# GenRF_R00.net
KiCad netlist of a schematic drawn in Altium Designer
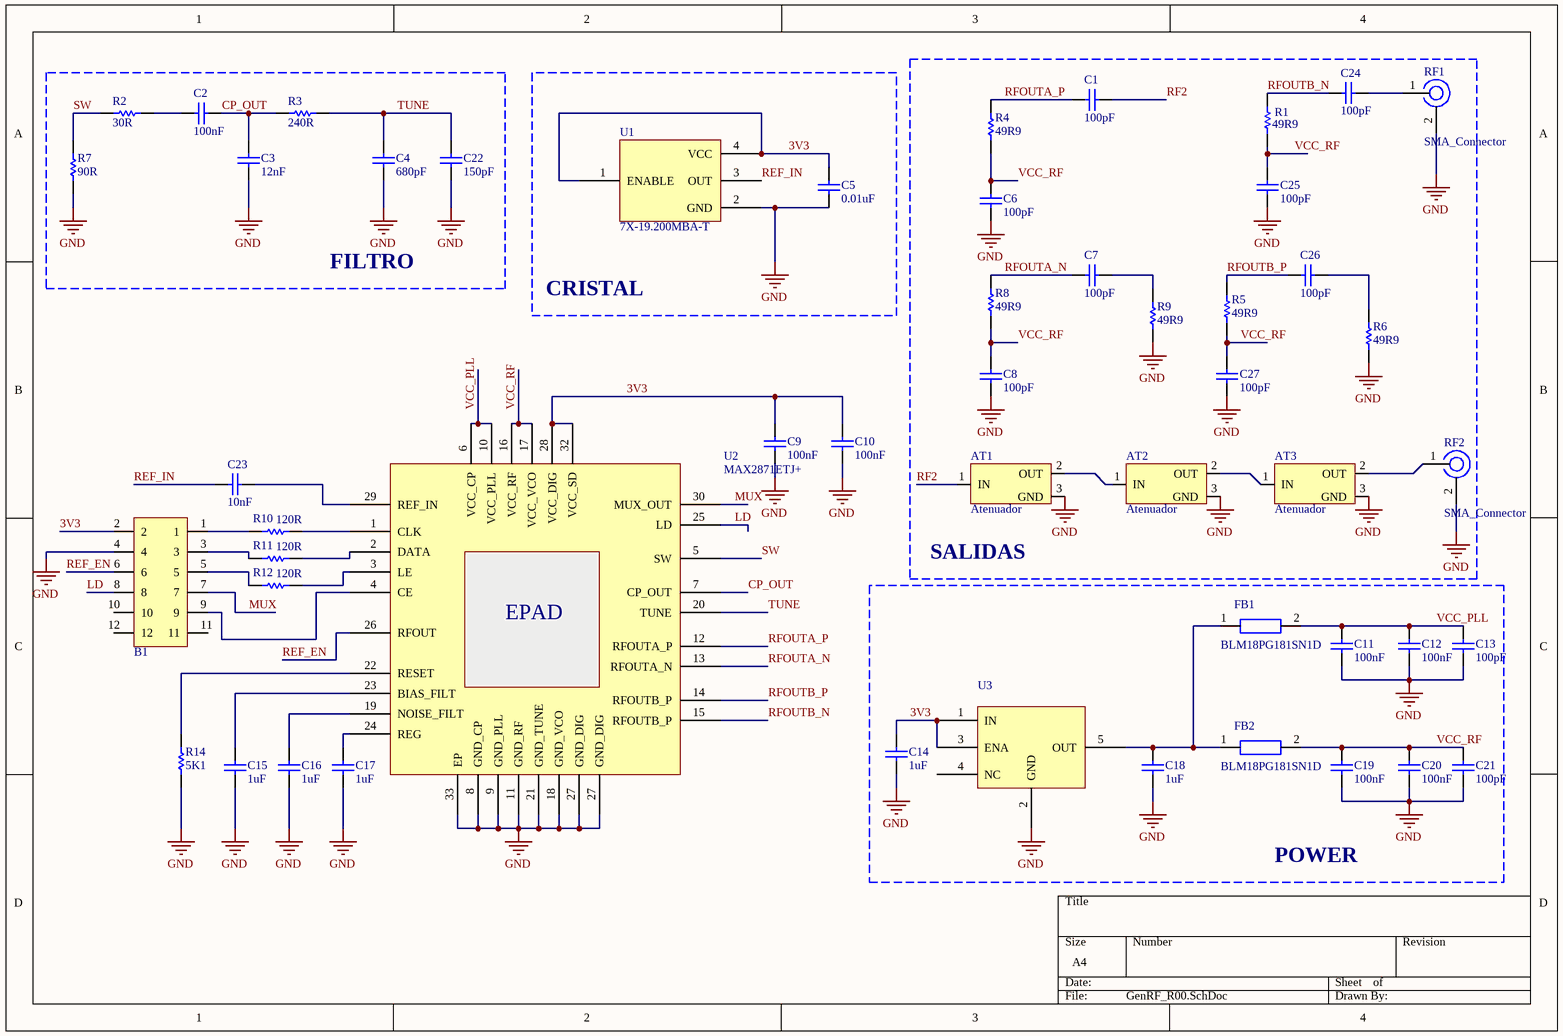
[diagram p0: GenRF_R00.SchDoc]

(export (version "E")
  (design (tool "Eeschema 10.0.6"))
  (components
    (comp (ref "AT1")
      (value "Atenuador")
      (footprint "Attenuator 0603")
      (libsource (lib "SchLib_PocketAnalyzer") (part "Atenuador"))
    )
    (comp (ref "AT2")
      (value "Atenuador")
      (footprint "Attenuator 0603")
      (libsource (lib "SchLib_PocketAnalyzer") (part "Atenuador"))
    )
    (comp (ref "AT3")
      (value "Atenuador")
      (footprint "Attenuator 0603")
      (libsource (lib "SchLib_PocketAnalyzer") (part "Atenuador"))
    )
    (comp (ref "B1")
      (value "Tira de pines de 12")
      (footprint "Header_M_2x6_0.1\"")
      (libsource (lib "GenRF_R00") (part "Headpin 10"))
    )
    (comp (ref "C1")
      (value "100pF")
      (footprint "C_0603")
      (description "Capacitor")
      (libsource (lib "Simulation Generic Components") (part "Capacitor"))
    )
    (comp (ref "C2")
      (value "100nF")
      (footprint "C_0805")
      (description "Capacitor")
      (libsource (lib "Simulation Generic Components") (part "Capacitor"))
    )
    (comp (ref "C3")
      (value "12nF")
      (footprint "C_0805")
      (description "Capacitor")
      (libsource (lib "Simulation Generic Components") (part "Capacitor"))
    )
    (comp (ref "C4")
      (value "680pF")
      (footprint "C_0805")
      (description "Capacitor")
      (libsource (lib "Simulation Generic Components") (part "Capacitor"))
    )
    (comp (ref "C5")
      (value "0.01uF")
      (footprint "C_0805")
      (description "Capacitor")
      (libsource (lib "Simulation Generic Components") (part "Capacitor"))
    )
    (comp (ref "C6")
      (value "100pF")
      (footprint "C_0805")
      (description "Capacitor")
      (libsource (lib "Simulation Generic Components") (part "Capacitor"))
    )
    (comp (ref "C7")
      (value "100pF")
      (footprint "C_0603")
      (description "Capacitor")
      (libsource (lib "Simulation Generic Components") (part "Capacitor"))
    )
    (comp (ref "C8")
      (value "100pF")
      (footprint "C_0805")
      (description "Capacitor")
      (libsource (lib "Simulation Generic Components") (part "Capacitor"))
    )
    (comp (ref "C9")
      (value "100nF")
      (footprint "C_0805")
      (description "Capacitor")
      (libsource (lib "Simulation Generic Components") (part "Capacitor"))
    )
    (comp (ref "C10")
      (value "100nF")
      (footprint "C_0805")
      (description "Capacitor")
      (libsource (lib "Simulation Generic Components") (part "Capacitor"))
    )
    (comp (ref "C11")
      (value "100nF")
      (footprint "C_0805")
      (description "Capacitor")
      (libsource (lib "Simulation Generic Components") (part "Capacitor"))
    )
    (comp (ref "C12")
      (value "100nF")
      (footprint "C_0805")
      (description "Capacitor")
      (libsource (lib "Simulation Generic Components") (part "Capacitor"))
    )
    (comp (ref "C13")
      (value "100pF")
      (footprint "C_0805")
      (description "Capacitor")
      (libsource (lib "Simulation Generic Components") (part "Capacitor"))
    )
    (comp (ref "C14")
      (value "1uF")
      (footprint "C_0805")
      (description "Capacitor")
      (libsource (lib "Simulation Generic Components") (part "Capacitor"))
    )
    (comp (ref "C15")
      (value "1uF")
      (footprint "C_0805")
      (description "Capacitor")
      (libsource (lib "Simulation Generic Components") (part "Capacitor"))
    )
    (comp (ref "C16")
      (value "1uF")
      (footprint "C_0805")
      (description "Capacitor")
      (libsource (lib "Simulation Generic Components") (part "Capacitor"))
    )
    (comp (ref "C17")
      (value "1uF")
      (footprint "C_0805")
      (description "Capacitor")
      (libsource (lib "Simulation Generic Components") (part "Capacitor"))
    )
    (comp (ref "C18")
      (value "1uF")
      (footprint "C_0805")
      (description "Capacitor")
      (libsource (lib "Simulation Generic Components") (part "Capacitor"))
    )
    (comp (ref "C19")
      (value "100nF")
      (footprint "C_0805")
      (description "Capacitor")
      (libsource (lib "Simulation Generic Components") (part "Capacitor"))
    )
    (comp (ref "C20")
      (value "100nF")
      (footprint "C_0805")
      (description "Capacitor")
      (libsource (lib "Simulation Generic Components") (part "Capacitor"))
    )
    (comp (ref "C21")
      (value "100pF")
      (footprint "C_0805")
      (description "Capacitor")
      (libsource (lib "Simulation Generic Components") (part "Capacitor"))
    )
    (comp (ref "C22")
      (value "150pF")
      (footprint "C_0805")
      (description "Capacitor")
      (libsource (lib "Simulation Generic Components") (part "Capacitor"))
    )
    (comp (ref "C23")
      (value "10nF")
      (footprint "C_0805")
      (description "Capacitor")
      (libsource (lib "Simulation Generic Components") (part "Capacitor"))
    )
    (comp (ref "C24")
      (value "100pF")
      (footprint "C_0603")
      (description "Capacitor")
      (libsource (lib "Simulation Generic Components") (part "Capacitor"))
    )
    (comp (ref "C25")
      (value "100pF")
      (footprint "C_0805")
      (description "Capacitor")
      (libsource (lib "Simulation Generic Components") (part "Capacitor"))
    )
    (comp (ref "C26")
      (value "100pF")
      (footprint "C_0603")
      (description "Capacitor")
      (libsource (lib "Simulation Generic Components") (part "Capacitor"))
    )
    (comp (ref "C27")
      (value "100pF")
      (footprint "C_0805")
      (description "Capacitor")
      (libsource (lib "Simulation Generic Components") (part "Capacitor"))
    )
    (comp (ref "FB1")
      (value "BLM18PG181SN1D")
      (footprint "FB_0603")
      (libsource (lib "GenRF_R00") (part "Ferrite Bead"))
    )
    (comp (ref "FB2")
      (value "BLM18PG181SN1D")
      (footprint "FB_0603")
      (libsource (lib "GenRF_R00") (part "Ferrite Bead"))
    )
    (comp (ref "R1")
      (value "49R9")
      (footprint "R_0603")
      (description "Resistor")
      (libsource (lib "Simulation Generic Components") (part "Resistor"))
    )
    (comp (ref "R2")
      (value "30R")
      (footprint "R_0805")
      (description "Resistor")
      (libsource (lib "Simulation Generic Components") (part "Resistor"))
    )
    (comp (ref "R3")
      (value "240R")
      (footprint "R_0805")
      (description "Resistor")
      (libsource (lib "Simulation Generic Components") (part "Resistor"))
    )
    (comp (ref "R4")
      (value "49R9")
      (footprint "R_0603")
      (description "Resistor")
      (libsource (lib "Simulation Generic Components") (part "Resistor"))
    )
    (comp (ref "R5")
      (value "49R9")
      (footprint "R_0603")
      (description "Resistor")
      (libsource (lib "Simulation Generic Components") (part "Resistor"))
    )
    (comp (ref "R6")
      (value "49R9")
      (footprint "R_0603")
      (description "Resistor")
      (libsource (lib "Simulation Generic Components") (part "Resistor"))
    )
    (comp (ref "R7")
      (value "90R")
      (footprint "R_0805")
      (description "Resistor")
      (libsource (lib "Simulation Generic Components") (part "Resistor"))
    )
    (comp (ref "R8")
      (value "49R9")
      (footprint "R_0603")
      (description "Resistor")
      (libsource (lib "Simulation Generic Components") (part "Resistor"))
    )
    (comp (ref "R9")
      (value "49R9")
      (footprint "R_0603")
      (description "Resistor")
      (libsource (lib "Simulation Generic Components") (part "Resistor"))
    )
    (comp (ref "R10")
      (value "120R")
      (footprint "R_0805")
      (description "Resistor")
      (libsource (lib "Simulation Generic Components") (part "Resistor"))
    )
    (comp (ref "R11")
      (value "120R")
      (footprint "R_0805")
      (description "Resistor")
      (libsource (lib "Simulation Generic Components") (part "Resistor"))
    )
    (comp (ref "R12")
      (value "120R")
      (footprint "R_0805")
      (description "Resistor")
      (libsource (lib "Simulation Generic Components") (part "Resistor"))
    )
    (comp (ref "R14")
      (value "5K1")
      (footprint "R_0805")
      (description "Resistor")
      (libsource (lib "Simulation Generic Components") (part "Resistor"))
    )
    (comp (ref "RF1")
      (value "SMA_Connector")
      (description "Connector SMA")
      (libsource (lib "SchLib_PocketAnalyzer") (part "SMA_Connector"))
    )
    (comp (ref "RF2")
      (value "SMA_Connector")
      (description "Connector SMA")
      (libsource (lib "SchLib_PocketAnalyzer") (part "SMA_Connector"))
    )
    (comp (ref "U1")
      (value "7X-19.200MBA-T")
      (footprint "XTAL")
      (description "XTAL OSC XO 19.2000MHZ CMOS SMD")
      (libsource (lib "GenRF_R00") (part "7X-19.200MBA-T"))
    )
    (comp (ref "U2")
      (value "MAX2871ETJ+")
      (footprint "MAX2870ETJ+")
      (libsource (lib "GenRF_R00") (part "MAX2871ETJ+"))
    )
    (comp (ref "U3")
      (value "LP5907QMFX-3.3")
      (footprint "TSOP")
      (description "IC REG LINEAR 3.3V 250MA SOT23-5")
      (libsource (lib "GenRF_R00") (part "LP5907QMFX-3.3"))
    )
  )
  (nets
    (net (code "1") (name "/3V3") (class "Default")
      (node (ref "B1") (pin "2") (pinfunction "2_2") (pintype "passive"))
      (node (ref "C10") (pin "2") (pinfunction "2_2") (pintype "passive"))
      (node (ref "C14") (pin "2") (pinfunction "2_2") (pintype "passive"))
      (node (ref "C5") (pin "1") (pinfunction "1_1") (pintype "passive"))
      (node (ref "C9") (pin "2") (pinfunction "2_2") (pintype "passive"))
      (node (ref "U1") (pin "1") (pinfunction "ENABLE_1") (pintype "passive"))
      (node (ref "U1") (pin "4") (pinfunction "VCC_4") (pintype "passive"))
      (node (ref "U2") (pin "28") (pinfunction "VCC_DIG_28") (pintype "passive"))
      (node (ref "U2") (pin "32") (pinfunction "VCC_SD_32") (pintype "passive"))
      (node (ref "U3") (pin "1") (pinfunction "IN_1") (pintype "passive"))
      (node (ref "U3") (pin "3") (pinfunction "ENA_3") (pintype "passive"))
    )
    (net (code "2") (name "/CP_OUT") (class "Default")
      (node (ref "C2") (pin "1") (pinfunction "1_1") (pintype "passive"))
      (node (ref "C3") (pin "2") (pinfunction "2_2") (pintype "passive"))
      (node (ref "R3") (pin "2") (pinfunction "2_2") (pintype "passive"))
      (node (ref "U2") (pin "7") (pinfunction "CP_OUT_7") (pintype "passive"))
    )
    (net (code "3") (name "/LD") (class "Default")
      (node (ref "B1") (pin "8") (pinfunction "8_8") (pintype "passive"))
      (node (ref "U2") (pin "25") (pinfunction "LD_25") (pintype "passive"))
    )
    (net (code "4") (name "/MUX") (class "Default")
      (node (ref "B1") (pin "7") (pinfunction "7_7") (pintype "passive"))
      (node (ref "U2") (pin "30") (pinfunction "MUX_OUT_30") (pintype "passive"))
    )
    (net (code "5") (name "/REF_EN") (class "Default")
      (node (ref "B1") (pin "6") (pinfunction "6_6") (pintype "passive"))
      (node (ref "U2") (pin "26") (pinfunction "RFOUT_26") (pintype "passive"))
    )
    (net (code "6") (name "/REF_IN") (class "Default")
      (node (ref "C23") (pin "2") (pinfunction "2_2") (pintype "passive"))
      (node (ref "U1") (pin "3") (pinfunction "OUT_3") (pintype "passive"))
    )
    (net (code "7") (name "/RF2") (class "Default")
      (node (ref "AT1") (pin "1") (pinfunction "IN_1") (pintype "passive"))
      (node (ref "C1") (pin "2") (pinfunction "2_2") (pintype "passive"))
    )
    (net (code "8") (name "/RFOUTA_N") (class "Default")
      (node (ref "C7") (pin "1") (pinfunction "1_1") (pintype "passive"))
      (node (ref "R8") (pin "2") (pinfunction "2_2") (pintype "passive"))
      (node (ref "U2") (pin "13") (pinfunction "RFOUTA_N_13") (pintype "passive"))
    )
    (net (code "9") (name "/RFOUTA_P") (class "Default")
      (node (ref "C1") (pin "1") (pinfunction "1_1") (pintype "passive"))
      (node (ref "R4") (pin "2") (pinfunction "2_2") (pintype "passive"))
      (node (ref "U2") (pin "12") (pinfunction "RFOUTA_P_12") (pintype "passive"))
    )
    (net (code "10") (name "/RFOUTB_N") (class "Default")
      (node (ref "C24") (pin "1") (pinfunction "1_1") (pintype "passive"))
      (node (ref "R1") (pin "2") (pinfunction "2_2") (pintype "passive"))
      (node (ref "U2") (pin "15") (pinfunction "RFOUTB_P_15") (pintype "passive"))
    )
    (net (code "11") (name "/RFOUTB_P") (class "Default")
      (node (ref "C26") (pin "1") (pinfunction "1_1") (pintype "passive"))
      (node (ref "R5") (pin "1") (pinfunction "1_1") (pintype "passive"))
      (node (ref "U2") (pin "14") (pinfunction "RFOUTB_P_14") (pintype "passive"))
    )
    (net (code "12") (name "/SW") (class "Default")
      (node (ref "R2") (pin "1") (pinfunction "1_1") (pintype "passive"))
      (node (ref "R7") (pin "1") (pinfunction "1_1") (pintype "passive"))
      (node (ref "U2") (pin "5") (pinfunction "SW_5") (pintype "passive"))
    )
    (net (code "13") (name "/TUNE") (class "Default")
      (node (ref "C22") (pin "2") (pinfunction "2_2") (pintype "passive"))
      (node (ref "C4") (pin "2") (pinfunction "2_2") (pintype "passive"))
      (node (ref "R3") (pin "1") (pinfunction "1_1") (pintype "passive"))
      (node (ref "U2") (pin "20") (pinfunction "TUNE_20") (pintype "passive"))
    )
    (net (code "14") (name "/VCC_PLL") (class "Default")
      (node (ref "C11") (pin "2") (pinfunction "2_2") (pintype "passive"))
      (node (ref "C12") (pin "2") (pinfunction "2_2") (pintype "passive"))
      (node (ref "C13") (pin "2") (pinfunction "2_2") (pintype "passive"))
      (node (ref "FB1") (pin "2") (pintype "passive"))
      (node (ref "U2") (pin "10") (pinfunction "VCC_PLL_10") (pintype "passive"))
      (node (ref "U2") (pin "6") (pinfunction "VCC_CP_6") (pintype "passive"))
    )
    (net (code "15") (name "/VCC_RF") (class "Default")
      (node (ref "C19") (pin "2") (pinfunction "2_2") (pintype "passive"))
      (node (ref "C20") (pin "2") (pinfunction "2_2") (pintype "passive"))
      (node (ref "C21") (pin "2") (pinfunction "2_2") (pintype "passive"))
      (node (ref "C25") (pin "1") (pinfunction "1_1") (pintype "passive"))
      (node (ref "C27") (pin "1") (pinfunction "1_1") (pintype "passive"))
      (node (ref "C6") (pin "1") (pinfunction "1_1") (pintype "passive"))
      (node (ref "C8") (pin "1") (pinfunction "1_1") (pintype "passive"))
      (node (ref "FB2") (pin "2") (pintype "passive"))
      (node (ref "R1") (pin "1") (pinfunction "1_1") (pintype "passive"))
      (node (ref "R4") (pin "1") (pinfunction "1_1") (pintype "passive"))
      (node (ref "R5") (pin "2") (pinfunction "2_2") (pintype "passive"))
      (node (ref "R8") (pin "1") (pinfunction "1_1") (pintype "passive"))
      (node (ref "U2") (pin "16") (pinfunction "VCC_RF_16") (pintype "passive"))
      (node (ref "U2") (pin "17") (pinfunction "VCC_VCO_17") (pintype "passive"))
    )
    (net (code "16") (name "GND") (class "Default")
      (node (ref "AT1") (pin "3") (pinfunction "GND_3") (pintype "passive"))
      (node (ref "AT2") (pin "3") (pinfunction "GND_3") (pintype "passive"))
      (node (ref "AT3") (pin "3") (pinfunction "GND_3") (pintype "passive"))
      (node (ref "B1") (pin "4") (pinfunction "4_4") (pintype "passive"))
      (node (ref "C10") (pin "1") (pinfunction "1_1") (pintype "passive"))
      (node (ref "C11") (pin "1") (pinfunction "1_1") (pintype "passive"))
      (node (ref "C12") (pin "1") (pinfunction "1_1") (pintype "passive"))
      (node (ref "C13") (pin "1") (pinfunction "1_1") (pintype "passive"))
      (node (ref "C14") (pin "1") (pinfunction "1_1") (pintype "passive"))
      (node (ref "C15") (pin "1") (pinfunction "1_1") (pintype "passive"))
      (node (ref "C16") (pin "1") (pinfunction "1_1") (pintype "passive"))
      (node (ref "C17") (pin "1") (pinfunction "1_1") (pintype "passive"))
      (node (ref "C18") (pin "1") (pinfunction "1_1") (pintype "passive"))
      (node (ref "C19") (pin "1") (pinfunction "1_1") (pintype "passive"))
      (node (ref "C20") (pin "1") (pinfunction "1_1") (pintype "passive"))
      (node (ref "C21") (pin "1") (pinfunction "1_1") (pintype "passive"))
      (node (ref "C22") (pin "1") (pinfunction "1_1") (pintype "passive"))
      (node (ref "C25") (pin "2") (pinfunction "2_2") (pintype "passive"))
      (node (ref "C27") (pin "2") (pinfunction "2_2") (pintype "passive"))
      (node (ref "C3") (pin "1") (pinfunction "1_1") (pintype "passive"))
      (node (ref "C4") (pin "1") (pinfunction "1_1") (pintype "passive"))
      (node (ref "C5") (pin "2") (pinfunction "2_2") (pintype "passive"))
      (node (ref "C6") (pin "2") (pinfunction "2_2") (pintype "passive"))
      (node (ref "C8") (pin "2") (pinfunction "2_2") (pintype "passive"))
      (node (ref "C9") (pin "1") (pinfunction "1_1") (pintype "passive"))
      (node (ref "R14") (pin "1") (pinfunction "1_1") (pintype "passive"))
      (node (ref "R6") (pin "2") (pinfunction "2_2") (pintype "passive"))
      (node (ref "R7") (pin "2") (pinfunction "2_2") (pintype "passive"))
      (node (ref "R9") (pin "2") (pinfunction "2_2") (pintype "passive"))
      (node (ref "RF1") (pin "2") (pinfunction "2_2") (pintype "passive"))
      (node (ref "RF2") (pin "2") (pinfunction "2_2") (pintype "passive"))
      (node (ref "U1") (pin "2") (pinfunction "GND_2") (pintype "passive"))
      (node (ref "U2") (pin "11") (pinfunction "GND_RF_11") (pintype "passive"))
      (node (ref "U2") (pin "18") (pinfunction "GND_VCO_18") (pintype "passive"))
      (node (ref "U2") (pin "21") (pinfunction "GND_TUNE_21") (pintype "passive"))
      (node (ref "U2") (pin "27") (pinfunction "GND_DIG_27") (pintype "passive"))
      (node (ref "U2") (pin "33") (pinfunction "EP_33") (pintype "passive"))
      (node (ref "U2") (pin "8") (pinfunction "GND_CP_8") (pintype "passive"))
      (node (ref "U2") (pin "9") (pinfunction "GND_PLL_9") (pintype "passive"))
      (node (ref "U3") (pin "2") (pinfunction "GND_2") (pintype "passive"))
    )
    (net (code "17") (name "Net-(AT1-OUT)") (class "Default")
      (node (ref "AT1") (pin "2") (pinfunction "OUT_2") (pintype "passive"))
      (node (ref "AT2") (pin "1") (pinfunction "IN_1") (pintype "passive"))
    )
    (net (code "18") (name "Net-(AT2-OUT)") (class "Default")
      (node (ref "AT2") (pin "2") (pinfunction "OUT_2") (pintype "passive"))
      (node (ref "AT3") (pin "1") (pinfunction "IN_1") (pintype "passive"))
    )
    (net (code "19") (name "Net-(AT3-OUT)") (class "Default")
      (node (ref "AT3") (pin "2") (pinfunction "OUT_2") (pintype "passive"))
      (node (ref "RF2") (pin "1") (pinfunction "1_1") (pintype "passive"))
    )
    (net (code "20") (name "Net-(B1-Pad1)") (class "Default")
      (node (ref "B1") (pin "1") (pinfunction "1_1") (pintype "passive"))
      (node (ref "R10") (pin "1") (pinfunction "1_1") (pintype "passive"))
    )
    (net (code "21") (name "Net-(B1-Pad3)") (class "Default")
      (node (ref "B1") (pin "3") (pinfunction "3_3") (pintype "passive"))
      (node (ref "R11") (pin "1") (pinfunction "1_1") (pintype "passive"))
    )
    (net (code "22") (name "Net-(B1-Pad5)") (class "Default")
      (node (ref "B1") (pin "5") (pinfunction "5_5") (pintype "passive"))
      (node (ref "R12") (pin "1") (pinfunction "1_1") (pintype "passive"))
    )
    (net (code "23") (name "Net-(C2-Pad2)") (class "Default")
      (node (ref "C2") (pin "2") (pinfunction "2_2") (pintype "passive"))
      (node (ref "R2") (pin "2") (pinfunction "2_2") (pintype "passive"))
    )
    (net (code "24") (name "Net-(C7-Pad2)") (class "Default")
      (node (ref "C7") (pin "2") (pinfunction "2_2") (pintype "passive"))
      (node (ref "R9") (pin "1") (pinfunction "1_1") (pintype "passive"))
    )
    (net (code "25") (name "Net-(C24-Pad2)") (class "Default")
      (node (ref "C24") (pin "2") (pinfunction "2_2") (pintype "passive"))
      (node (ref "RF1") (pin "1") (pinfunction "1_1") (pintype "passive"))
    )
    (net (code "26") (name "Net-(C26-Pad2)") (class "Default")
      (node (ref "C26") (pin "2") (pinfunction "2_2") (pintype "passive"))
      (node (ref "R6") (pin "1") (pinfunction "1_1") (pintype "passive"))
    )
    (net (code "27") (name "Net-(U2-BIAS_FILT)") (class "Default")
      (node (ref "C15") (pin "2") (pinfunction "2_2") (pintype "passive"))
      (node (ref "U2") (pin "23") (pinfunction "BIAS_FILT_23") (pintype "passive"))
    )
    (net (code "28") (name "Net-(U2-CE)") (class "Default")
      (node (ref "B1") (pin "9") (pinfunction "9_9") (pintype "passive"))
      (node (ref "U2") (pin "4") (pinfunction "CE_4") (pintype "passive"))
    )
    (net (code "29") (name "Net-(U2-CLK)") (class "Default")
      (node (ref "R10") (pin "2") (pinfunction "2_2") (pintype "passive"))
      (node (ref "U2") (pin "1") (pinfunction "CLK_1") (pintype "passive"))
    )
    (net (code "30") (name "Net-(U2-DATA)") (class "Default")
      (node (ref "R11") (pin "2") (pinfunction "2_2") (pintype "passive"))
      (node (ref "U2") (pin "2") (pinfunction "DATA_2") (pintype "passive"))
    )
    (net (code "31") (name "Net-(U2-LE)") (class "Default")
      (node (ref "R12") (pin "2") (pinfunction "2_2") (pintype "passive"))
      (node (ref "U2") (pin "3") (pinfunction "LE_3") (pintype "passive"))
    )
    (net (code "32") (name "Net-(U2-NOISE_FILT)") (class "Default")
      (node (ref "C16") (pin "2") (pinfunction "2_2") (pintype "passive"))
      (node (ref "U2") (pin "19") (pinfunction "NOISE_FILT_19") (pintype "passive"))
    )
    (net (code "33") (name "Net-(U2-REF_IN)") (class "Default")
      (node (ref "C23") (pin "1") (pinfunction "1_1") (pintype "passive"))
      (node (ref "U2") (pin "29") (pinfunction "REF_IN_29") (pintype "passive"))
    )
    (net (code "34") (name "Net-(U2-REG)") (class "Default")
      (node (ref "C17") (pin "2") (pinfunction "2_2") (pintype "passive"))
      (node (ref "U2") (pin "24") (pinfunction "REG_24") (pintype "passive"))
    )
    (net (code "35") (name "Net-(U2-RESET)") (class "Default")
      (node (ref "R14") (pin "2") (pinfunction "2_2") (pintype "passive"))
      (node (ref "U2") (pin "22") (pinfunction "RESET_22") (pintype "passive"))
    )
    (net (code "36") (name "Net-(U3-OUT)") (class "Default")
      (node (ref "C18") (pin "2") (pinfunction "2_2") (pintype "passive"))
      (node (ref "FB1") (pin "1") (pintype "passive"))
      (node (ref "FB2") (pin "1") (pintype "passive"))
      (node (ref "U3") (pin "5") (pinfunction "OUT_5") (pintype "passive"))
    )
    (net (code "37") (name "unconnected-(B1-Pad10)") (class "Default")
      (node (ref "B1") (pin "10") (pinfunction "10_10") (pintype "passive"))
    )
    (net (code "38") (name "unconnected-(B1-Pad11)") (class "Default")
      (node (ref "B1") (pin "11") (pinfunction "11_11") (pintype "passive"))
    )
    (net (code "39") (name "unconnected-(B1-Pad12)") (class "Default")
      (node (ref "B1") (pin "12") (pinfunction "12_12") (pintype "passive"))
    )
    (net (code "40") (name "unconnected-(U3-NC-Pad4)") (class "Default")
      (node (ref "U3") (pin "4") (pinfunction "NC_4") (pintype "passive"))
    )
  )
)
